# driver_32bit_v1_1.net
KiCad netlist of a schematic drawn in EAGLE
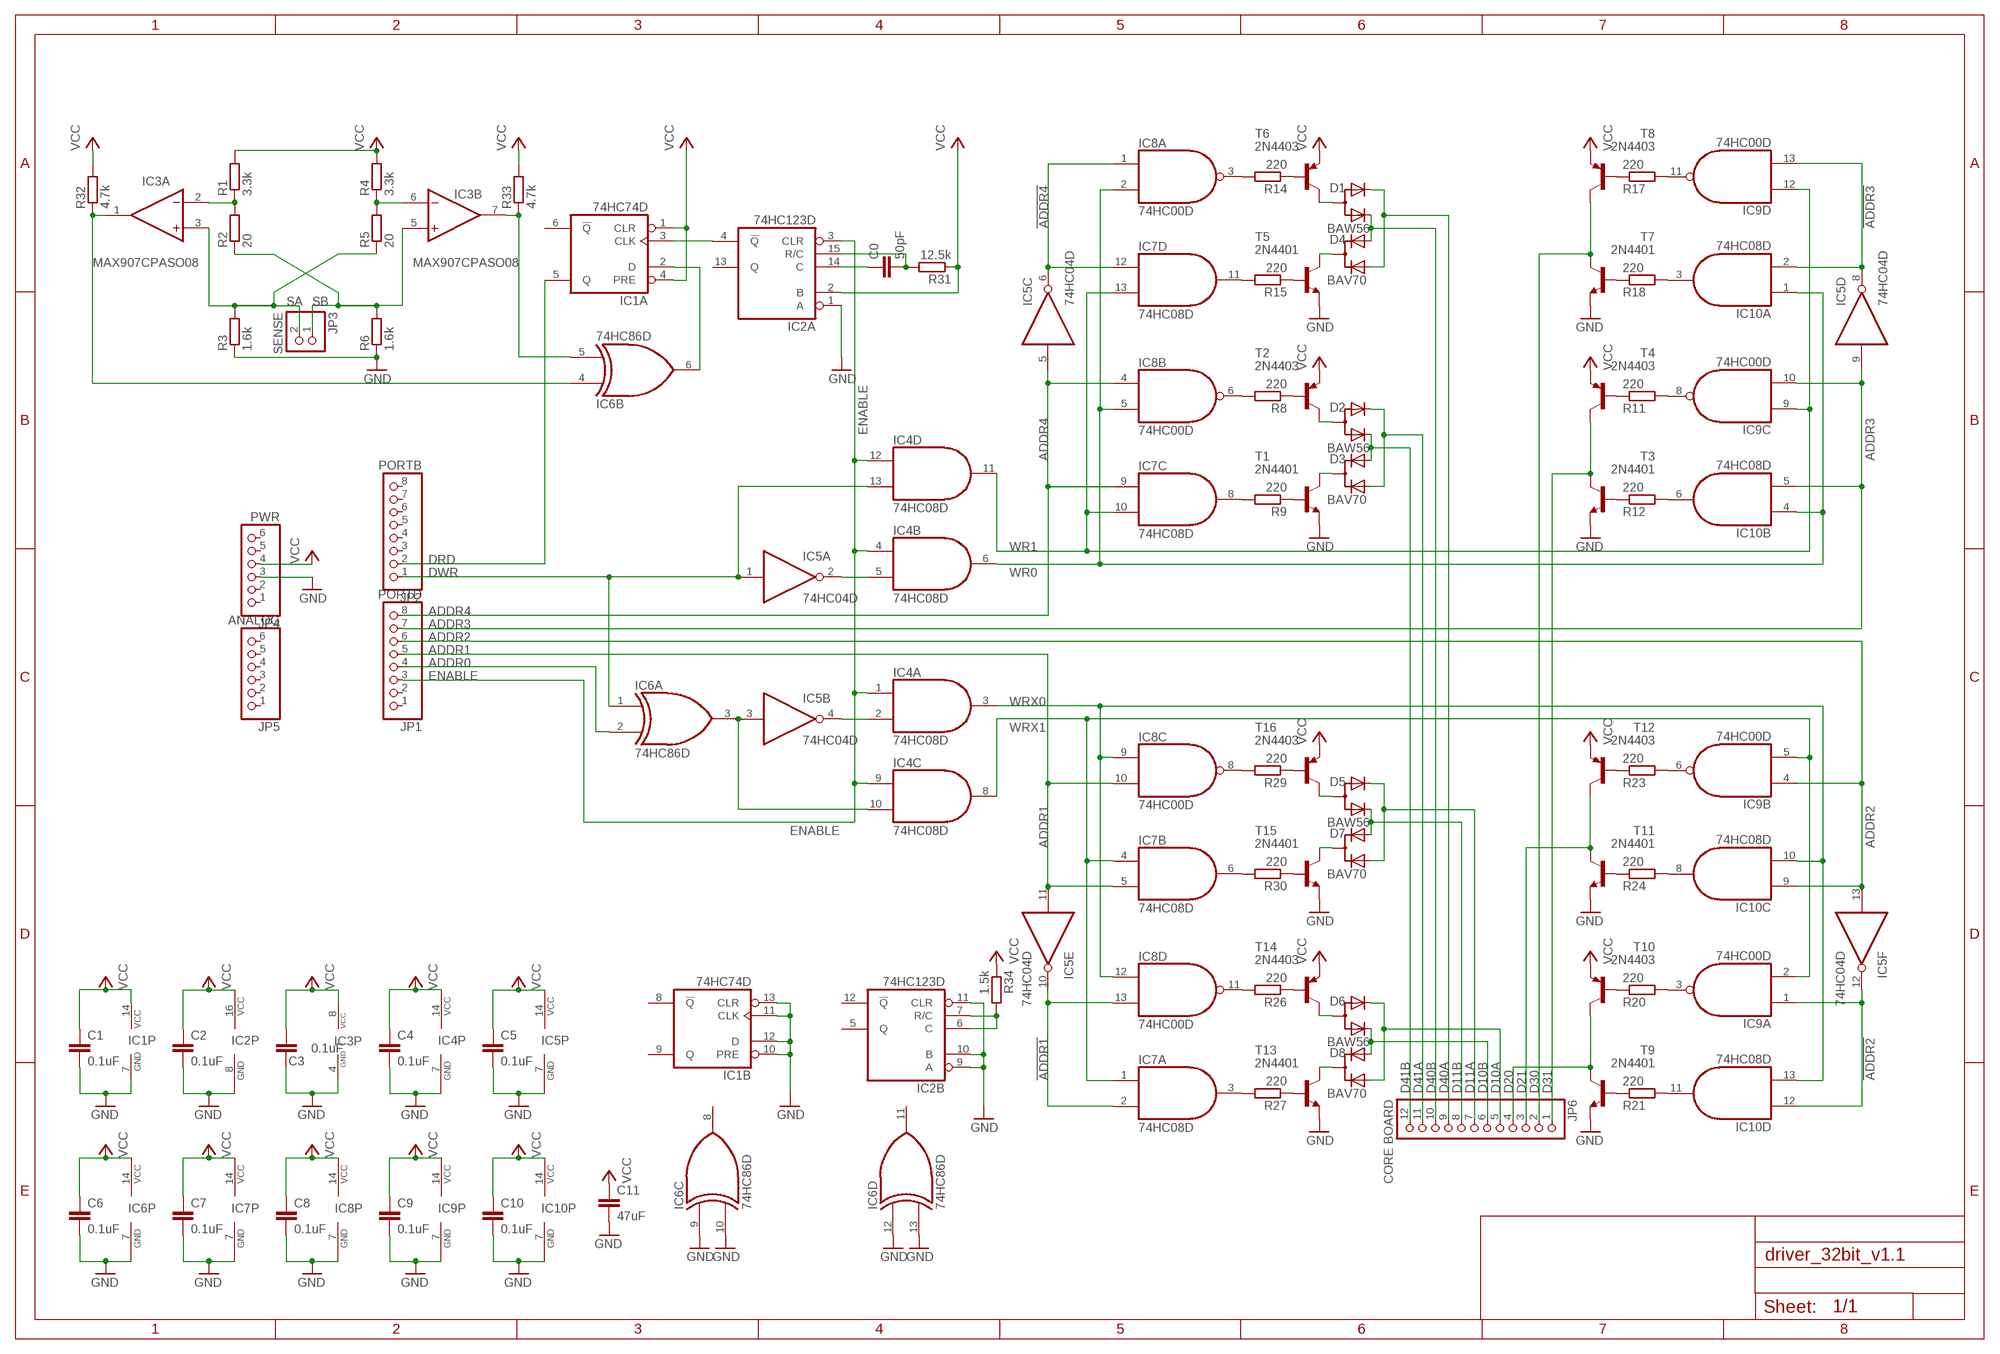
[diagram p0: schematic, sheet 1]

(export (version "E")
  (design (tool "Eeschema 10.0.6"))
  (components
    (comp (ref "C0")
      (value "50pF")
      (footprint "eagle-import:C1206")
      (libsource (lib "eagle-import") (part "C-EUC1206"))
    )
    (comp (ref "C1")
      (value "0.1uF")
      (footprint "eagle-import:C1206")
      (libsource (lib "eagle-import") (part "C-EUC1206"))
    )
    (comp (ref "C2")
      (value "0.1uF")
      (footprint "eagle-import:C1206")
      (libsource (lib "eagle-import") (part "C-EUC1206"))
    )
    (comp (ref "C3")
      (value "0.1uF")
      (footprint "eagle-import:C1206")
      (libsource (lib "eagle-import") (part "C-EUC1206"))
    )
    (comp (ref "C4")
      (value "0.1uF")
      (footprint "eagle-import:C1206")
      (libsource (lib "eagle-import") (part "C-EUC1206"))
    )
    (comp (ref "C5")
      (value "0.1uF")
      (footprint "eagle-import:C1206")
      (libsource (lib "eagle-import") (part "C-EUC1206"))
    )
    (comp (ref "C6")
      (value "0.1uF")
      (footprint "eagle-import:C1206")
      (libsource (lib "eagle-import") (part "C-EUC1206"))
    )
    (comp (ref "C7")
      (value "0.1uF")
      (footprint "eagle-import:C1206")
      (libsource (lib "eagle-import") (part "C-EUC1206"))
    )
    (comp (ref "C8")
      (value "0.1uF")
      (footprint "eagle-import:C1206")
      (libsource (lib "eagle-import") (part "C-EUC1206"))
    )
    (comp (ref "C9")
      (value "0.1uF")
      (footprint "eagle-import:C1206")
      (libsource (lib "eagle-import") (part "C-EUC1206"))
    )
    (comp (ref "C10")
      (value "0.1uF")
      (footprint "eagle-import:C1206")
      (libsource (lib "eagle-import") (part "C-EUC1206"))
    )
    (comp (ref "C11")
      (value "47uF")
      (footprint "eagle-import:C1206")
      (libsource (lib "eagle-import") (part "C-EUC1206"))
    )
    (comp (ref "D1")
      (value "BAW56")
      (footprint "eagle-import:SOT23")
      (libsource (lib "eagle-import") (part "DIODE-2CA|ACSOT23"))
    )
    (comp (ref "D2")
      (value "BAW56")
      (footprint "eagle-import:SOT23")
      (libsource (lib "eagle-import") (part "DIODE-2CA|ACSOT23"))
    )
    (comp (ref "D3")
      (value "BAV70")
      (footprint "eagle-import:SOT23")
      (libsource (lib "eagle-import") (part "DIODE-2AC|CASOT23"))
    )
    (comp (ref "D4")
      (value "BAV70")
      (footprint "eagle-import:SOT23")
      (libsource (lib "eagle-import") (part "DIODE-2AC|CASOT23"))
    )
    (comp (ref "D5")
      (value "BAW56")
      (footprint "eagle-import:SOT23")
      (libsource (lib "eagle-import") (part "DIODE-2CA|ACSOT23"))
    )
    (comp (ref "D6")
      (value "BAW56")
      (footprint "eagle-import:SOT23")
      (libsource (lib "eagle-import") (part "DIODE-2CA|ACSOT23"))
    )
    (comp (ref "D7")
      (value "BAV70")
      (footprint "eagle-import:SOT23")
      (libsource (lib "eagle-import") (part "DIODE-2AC|CASOT23"))
    )
    (comp (ref "D8")
      (value "BAV70")
      (footprint "eagle-import:SOT23")
      (libsource (lib "eagle-import") (part "DIODE-2AC|CASOT23"))
    )
    (comp (ref "IC1")
      (value "74HC74D")
      (footprint "eagle-import:SO14")
      (fields
        (field (name "MF") "TEXAS INSTRUMENTS")
        (field (name "MPN") "SN74HC74D")
        (field (name "OC_NEWARK") "08F6568")
      )
      (libsource (lib "eagle-import") (part "7474DHC"))
    )
    (comp (ref "IC2")
      (value "74HC123D")
      (footprint "eagle-import:SO16")
      (fields (field (name "MPN") "74HC123D") (field (name "OC_NEWARK") "99K0580"))
      (libsource (lib "eagle-import") (part "74123D"))
    )
    (comp (ref "IC3")
      (value "MAX907CPASO08")
      (footprint "eagle-import:SO08")
      (fields (field (name "OC_NEWARK") "unknown"))
      (libsource (lib "eagle-import") (part "MAX907CPASO08"))
    )
    (comp (ref "IC4")
      (value "74HC08D")
      (footprint "eagle-import:SO14")
      (fields
        (field (name "MF") "TEXAS INSTRUMENTS")
        (field (name "MPN") "SN74HC08D")
        (field (name "OC_NEWARK") "36K3552")
      )
      (libsource (lib "eagle-import") (part "7408DALS"))
    )
    (comp (ref "IC5")
      (value "74HC04D")
      (footprint "eagle-import:SO14")
      (fields
        (field (name "MF") "TEXAS INSTRUMENTS")
        (field (name "MPN") "SN74HC04D")
        (field (name "OC_NEWARK") "72K9430")
      )
      (libsource (lib "eagle-import") (part "7404DALS"))
    )
    (comp (ref "IC6")
      (value "74HC86D")
      (footprint "eagle-import:SO14")
      (fields (field (name "MPN") "74HC86D") (field (name "OC_NEWARK") "99K0602"))
      (libsource (lib "eagle-import") (part "7486DLS"))
    )
    (comp (ref "IC7")
      (value "74HC08D")
      (footprint "eagle-import:SO14")
      (fields
        (field (name "MF") "TEXAS INSTRUMENTS")
        (field (name "MPN") "SN74HC08D")
        (field (name "OC_NEWARK") "36K3552")
      )
      (libsource (lib "eagle-import") (part "7408DALS"))
    )
    (comp (ref "IC8")
      (value "74HC00D")
      (footprint "eagle-import:SO14")
      (fields (field (name "MPN") "74HC00D-Q100,118") (field (name "OC_NEWARK") "85X2859"))
      (libsource (lib "eagle-import") (part "7400DALS"))
    )
    (comp (ref "IC9")
      (value "74HC00D")
      (footprint "eagle-import:SO14")
      (fields (field (name "MPN") "74HC00D-Q100,118") (field (name "OC_NEWARK") "85X2859"))
      (libsource (lib "eagle-import") (part "7400DALS"))
    )
    (comp (ref "IC10")
      (value "74HC08D")
      (footprint "eagle-import:SO14")
      (fields
        (field (name "MF") "TEXAS INSTRUMENTS")
        (field (name "MPN") "SN74HC08D")
        (field (name "OC_NEWARK") "36K3552")
      )
      (libsource (lib "eagle-import") (part "7408DALS"))
    )
    (comp (ref "JP1")
      (value "PORTD")
      (footprint "eagle-import:1X08")
      (libsource (lib "eagle-import") (part "PINHD-1X8"))
    )
    (comp (ref "JP2")
      (value "PORTB")
      (footprint "eagle-import:1X08")
      (libsource (lib "eagle-import") (part "PINHD-1X8"))
    )
    (comp (ref "JP3")
      (value "SENSE")
      (footprint "eagle-import:1X02")
      (libsource (lib "eagle-import") (part "PINHD-1X2"))
    )
    (comp (ref "JP4")
      (value "PWR")
      (footprint "eagle-import:1X06")
      (libsource (lib "eagle-import") (part "PINHD-1X6"))
    )
    (comp (ref "JP5")
      (value "ANALOG")
      (footprint "eagle-import:1X06")
      (libsource (lib "eagle-import") (part "PINHD-1X6"))
    )
    (comp (ref "JP6")
      (value "CORE BOARD")
      (footprint "eagle-import:1X12")
      (libsource (lib "eagle-import") (part "PINHD-1X12"))
    )
    (comp (ref "R1")
      (value "3.3k")
      (footprint "eagle-import:R1206")
      (libsource (lib "eagle-import") (part "R-EU_R1206"))
    )
    (comp (ref "R2")
      (value "20")
      (footprint "eagle-import:R1206")
      (libsource (lib "eagle-import") (part "R-EU_R1206"))
    )
    (comp (ref "R3")
      (value "1.6k")
      (footprint "eagle-import:R1206")
      (libsource (lib "eagle-import") (part "R-EU_R1206"))
    )
    (comp (ref "R4")
      (value "3.3k")
      (footprint "eagle-import:R1206")
      (libsource (lib "eagle-import") (part "R-EU_R1206"))
    )
    (comp (ref "R5")
      (value "20")
      (footprint "eagle-import:R1206")
      (libsource (lib "eagle-import") (part "R-EU_R1206"))
    )
    (comp (ref "R6")
      (value "1.6k")
      (footprint "eagle-import:R1206")
      (libsource (lib "eagle-import") (part "R-EU_R1206"))
    )
    (comp (ref "R8")
      (value "220")
      (footprint "eagle-import:R1206")
      (libsource (lib "eagle-import") (part "R-EU_R1206"))
    )
    (comp (ref "R9")
      (value "220")
      (footprint "eagle-import:R1206")
      (libsource (lib "eagle-import") (part "R-EU_R1206"))
    )
    (comp (ref "R11")
      (value "220")
      (footprint "eagle-import:R1206")
      (libsource (lib "eagle-import") (part "R-EU_R1206"))
    )
    (comp (ref "R12")
      (value "220")
      (footprint "eagle-import:R1206")
      (libsource (lib "eagle-import") (part "R-EU_R1206"))
    )
    (comp (ref "R14")
      (value "220")
      (footprint "eagle-import:R1206")
      (libsource (lib "eagle-import") (part "R-EU_R1206"))
    )
    (comp (ref "R15")
      (value "220")
      (footprint "eagle-import:R1206")
      (libsource (lib "eagle-import") (part "R-EU_R1206"))
    )
    (comp (ref "R17")
      (value "220")
      (footprint "eagle-import:R1206")
      (libsource (lib "eagle-import") (part "R-EU_R1206"))
    )
    (comp (ref "R18")
      (value "220")
      (footprint "eagle-import:R1206")
      (libsource (lib "eagle-import") (part "R-EU_R1206"))
    )
    (comp (ref "R20")
      (value "220")
      (footprint "eagle-import:R1206")
      (libsource (lib "eagle-import") (part "R-EU_R1206"))
    )
    (comp (ref "R21")
      (value "220")
      (footprint "eagle-import:R1206")
      (libsource (lib "eagle-import") (part "R-EU_R1206"))
    )
    (comp (ref "R23")
      (value "220")
      (footprint "eagle-import:R1206")
      (libsource (lib "eagle-import") (part "R-EU_R1206"))
    )
    (comp (ref "R24")
      (value "220")
      (footprint "eagle-import:R1206")
      (libsource (lib "eagle-import") (part "R-EU_R1206"))
    )
    (comp (ref "R26")
      (value "220")
      (footprint "eagle-import:R1206")
      (libsource (lib "eagle-import") (part "R-EU_R1206"))
    )
    (comp (ref "R27")
      (value "220")
      (footprint "eagle-import:R1206")
      (libsource (lib "eagle-import") (part "R-EU_R1206"))
    )
    (comp (ref "R29")
      (value "220")
      (footprint "eagle-import:R1206")
      (libsource (lib "eagle-import") (part "R-EU_R1206"))
    )
    (comp (ref "R30")
      (value "220")
      (footprint "eagle-import:R1206")
      (libsource (lib "eagle-import") (part "R-EU_R1206"))
    )
    (comp (ref "R31")
      (value "12.5k")
      (footprint "eagle-import:R1206")
      (libsource (lib "eagle-import") (part "R-EU_R1206"))
    )
    (comp (ref "R32")
      (value "4.7k")
      (footprint "eagle-import:R1206")
      (libsource (lib "eagle-import") (part "R-EU_R1206"))
    )
    (comp (ref "R33")
      (value "4.7k")
      (footprint "eagle-import:R1206")
      (libsource (lib "eagle-import") (part "R-EU_R1206"))
    )
    (comp (ref "R34")
      (value "1.5k")
      (footprint "eagle-import:R1206")
      (libsource (lib "eagle-import") (part "R-EU_R1206"))
    )
    (comp (ref "T1")
      (value "2N4401")
      (footprint "eagle-import:SOT23-BEC")
      (fields (field (name "MF") "ON SEMICONDUCTOR") (field (name "MPN") "2N4401RLRPG"))
      (libsource (lib "eagle-import") (part "-NPN-SOT23-BECMMBT4401LT1"))
    )
    (comp (ref "T2")
      (value "2N4403")
      (footprint "eagle-import:SOT23-BEC")
      (libsource (lib "eagle-import") (part "-PNP-SOT23-BECMMBT4403LT1"))
    )
    (comp (ref "T3")
      (value "2N4401")
      (footprint "eagle-import:SOT23-BEC")
      (fields (field (name "MF") "ON SEMICONDUCTOR") (field (name "MPN") "2N4401RLRPG"))
      (libsource (lib "eagle-import") (part "-NPN-SOT23-BECMMBT4401LT1"))
    )
    (comp (ref "T4")
      (value "2N4403")
      (footprint "eagle-import:SOT23-BEC")
      (libsource (lib "eagle-import") (part "-PNP-SOT23-BECMMBT4403LT1"))
    )
    (comp (ref "T5")
      (value "2N4401")
      (footprint "eagle-import:SOT23-BEC")
      (fields (field (name "MF") "ON SEMICONDUCTOR") (field (name "MPN") "2N4401RLRPG"))
      (libsource (lib "eagle-import") (part "-NPN-SOT23-BECMMBT4401LT1"))
    )
    (comp (ref "T6")
      (value "2N4403")
      (footprint "eagle-import:SOT23-BEC")
      (libsource (lib "eagle-import") (part "-PNP-SOT23-BECMMBT4403LT1"))
    )
    (comp (ref "T7")
      (value "2N4401")
      (footprint "eagle-import:SOT23-BEC")
      (fields (field (name "MF") "ON SEMICONDUCTOR") (field (name "MPN") "2N4401RLRPG"))
      (libsource (lib "eagle-import") (part "-NPN-SOT23-BECMMBT4401LT1"))
    )
    (comp (ref "T8")
      (value "2N4403")
      (footprint "eagle-import:SOT23-BEC")
      (libsource (lib "eagle-import") (part "-PNP-SOT23-BECMMBT4403LT1"))
    )
    (comp (ref "T9")
      (value "2N4401")
      (footprint "eagle-import:SOT23-BEC")
      (fields (field (name "MF") "ON SEMICONDUCTOR") (field (name "MPN") "2N4401RLRPG"))
      (libsource (lib "eagle-import") (part "-NPN-SOT23-BECMMBT4401LT1"))
    )
    (comp (ref "T10")
      (value "2N4403")
      (footprint "eagle-import:SOT23-BEC")
      (libsource (lib "eagle-import") (part "-PNP-SOT23-BECMMBT4403LT1"))
    )
    (comp (ref "T11")
      (value "2N4401")
      (footprint "eagle-import:SOT23-BEC")
      (fields (field (name "MF") "ON SEMICONDUCTOR") (field (name "MPN") "2N4401RLRPG"))
      (libsource (lib "eagle-import") (part "-NPN-SOT23-BECMMBT4401LT1"))
    )
    (comp (ref "T12")
      (value "2N4403")
      (footprint "eagle-import:SOT23-BEC")
      (libsource (lib "eagle-import") (part "-PNP-SOT23-BECMMBT4403LT1"))
    )
    (comp (ref "T13")
      (value "2N4401")
      (footprint "eagle-import:SOT23-BEC")
      (fields (field (name "MF") "ON SEMICONDUCTOR") (field (name "MPN") "2N4401RLRPG"))
      (libsource (lib "eagle-import") (part "-NPN-SOT23-BECMMBT4401LT1"))
    )
    (comp (ref "T14")
      (value "2N4403")
      (footprint "eagle-import:SOT23-BEC")
      (libsource (lib "eagle-import") (part "-PNP-SOT23-BECMMBT4403LT1"))
    )
    (comp (ref "T15")
      (value "2N4401")
      (footprint "eagle-import:SOT23-BEC")
      (fields (field (name "MF") "ON SEMICONDUCTOR") (field (name "MPN") "2N4401RLRPG"))
      (libsource (lib "eagle-import") (part "-NPN-SOT23-BECMMBT4401LT1"))
    )
    (comp (ref "T16")
      (value "2N4403")
      (footprint "eagle-import:SOT23-BEC")
      (libsource (lib "eagle-import") (part "-PNP-SOT23-BECMMBT4403LT1"))
    )
  )
  (nets
    (net (code "1") (name "/ADDR0") (class "Default")
      (node (ref "IC6") (pin "2") (pinfunction "I1_2") (pintype "input"))
      (node (ref "JP1") (pin "4") (pinfunction "4_4") (pintype "passive"))
    )
    (net (code "2") (name "/ADDR1") (class "Default")
      (node (ref "IC5") (pin "11") (pinfunction "I_11") (pintype "input"))
      (node (ref "IC7") (pin "5") (pinfunction "I1_5") (pintype "input"))
      (node (ref "IC8") (pin "10") (pinfunction "I1_10") (pintype "input"))
      (node (ref "JP1") (pin "5") (pinfunction "5_5") (pintype "passive"))
    )
    (net (code "3") (name "/ADDR2") (class "Default")
      (node (ref "IC10") (pin "9") (pinfunction "I0_9") (pintype "input"))
      (node (ref "IC5") (pin "13") (pinfunction "I_13") (pintype "input"))
      (node (ref "IC9") (pin "4") (pinfunction "I0_4") (pintype "input"))
      (node (ref "JP1") (pin "6") (pinfunction "6_6") (pintype "passive"))
    )
    (net (code "4") (name "/ADDR3") (class "Default")
      (node (ref "IC10") (pin "5") (pinfunction "I1_5") (pintype "input"))
      (node (ref "IC5") (pin "9") (pinfunction "I_9") (pintype "input"))
      (node (ref "IC9") (pin "10") (pinfunction "I1_10") (pintype "input"))
      (node (ref "JP1") (pin "7") (pinfunction "7_7") (pintype "passive"))
    )
    (net (code "5") (name "/ADDR4") (class "Default")
      (node (ref "IC5") (pin "5") (pinfunction "I_5") (pintype "input"))
      (node (ref "IC7") (pin "9") (pinfunction "I0_9") (pintype "input"))
      (node (ref "IC8") (pin "4") (pinfunction "I0_4") (pintype "input"))
      (node (ref "JP1") (pin "8") (pinfunction "8_8") (pintype "passive"))
    )
    (net (code "6") (name "/D10A") (class "Default")
      (node (ref "D6") (pin "1") (pinfunction "K2_1") (pintype "passive"))
      (node (ref "D8") (pin "2") (pinfunction "A2_2") (pintype "passive"))
      (node (ref "JP6") (pin "5") (pinfunction "5_5") (pintype "passive"))
    )
    (net (code "7") (name "/D10B") (class "Default")
      (node (ref "D6") (pin "2") (pinfunction "K1_2") (pintype "passive"))
      (node (ref "D8") (pin "1") (pinfunction "A1_1") (pintype "passive"))
      (node (ref "JP6") (pin "6") (pinfunction "6_6") (pintype "passive"))
    )
    (net (code "8") (name "/D11A") (class "Default")
      (node (ref "D5") (pin "1") (pinfunction "K2_1") (pintype "passive"))
      (node (ref "D7") (pin "2") (pinfunction "A2_2") (pintype "passive"))
      (node (ref "JP6") (pin "7") (pinfunction "7_7") (pintype "passive"))
    )
    (net (code "9") (name "/D11B") (class "Default")
      (node (ref "D5") (pin "2") (pinfunction "K1_2") (pintype "passive"))
      (node (ref "D7") (pin "1") (pinfunction "A1_1") (pintype "passive"))
      (node (ref "JP6") (pin "8") (pinfunction "8_8") (pintype "passive"))
    )
    (net (code "10") (name "/D20") (class "Default")
      (node (ref "JP6") (pin "4") (pinfunction "4_4") (pintype "passive"))
      (node (ref "T10") (pin "C") (pinfunction "C_C") (pintype "passive"))
      (node (ref "T9") (pin "C") (pinfunction "C_C") (pintype "passive"))
    )
    (net (code "11") (name "/D21") (class "Default")
      (node (ref "JP6") (pin "3") (pinfunction "3_3") (pintype "passive"))
      (node (ref "T11") (pin "C") (pinfunction "C_C") (pintype "passive"))
      (node (ref "T12") (pin "C") (pinfunction "C_C") (pintype "passive"))
    )
    (net (code "12") (name "/D30") (class "Default")
      (node (ref "JP6") (pin "2") (pinfunction "2_2") (pintype "passive"))
      (node (ref "T7") (pin "C") (pinfunction "C_C") (pintype "passive"))
      (node (ref "T8") (pin "C") (pinfunction "C_C") (pintype "passive"))
    )
    (net (code "13") (name "/D31") (class "Default")
      (node (ref "JP6") (pin "1") (pinfunction "1_1") (pintype "passive"))
      (node (ref "T3") (pin "C") (pinfunction "C_C") (pintype "passive"))
      (node (ref "T4") (pin "C") (pinfunction "C_C") (pintype "passive"))
    )
    (net (code "14") (name "/D40A") (class "Default")
      (node (ref "D1") (pin "1") (pinfunction "K2_1") (pintype "passive"))
      (node (ref "D4") (pin "2") (pinfunction "A2_2") (pintype "passive"))
      (node (ref "JP6") (pin "9") (pinfunction "9_9") (pintype "passive"))
    )
    (net (code "15") (name "/D40B") (class "Default")
      (node (ref "D1") (pin "2") (pinfunction "K1_2") (pintype "passive"))
      (node (ref "D4") (pin "1") (pinfunction "A1_1") (pintype "passive"))
      (node (ref "JP6") (pin "10") (pinfunction "10_10") (pintype "passive"))
    )
    (net (code "16") (name "/D41A") (class "Default")
      (node (ref "D2") (pin "1") (pinfunction "K2_1") (pintype "passive"))
      (node (ref "D3") (pin "2") (pinfunction "A2_2") (pintype "passive"))
      (node (ref "JP6") (pin "11") (pinfunction "11_11") (pintype "passive"))
    )
    (net (code "17") (name "/D41B") (class "Default")
      (node (ref "D2") (pin "2") (pinfunction "K1_2") (pintype "passive"))
      (node (ref "D3") (pin "1") (pinfunction "A1_1") (pintype "passive"))
      (node (ref "JP6") (pin "12") (pinfunction "12_12") (pintype "passive"))
    )
    (net (code "18") (name "/DRD") (class "Default")
      (node (ref "IC1") (pin "5") (pinfunction "Q_5") (pintype "output"))
      (node (ref "JP2") (pin "2") (pinfunction "2_2") (pintype "passive"))
    )
    (net (code "19") (name "/DWR") (class "Default")
      (node (ref "IC4") (pin "13") (pinfunction "I1_13") (pintype "input"))
      (node (ref "IC5") (pin "1") (pinfunction "I_1") (pintype "input"))
      (node (ref "IC6") (pin "1") (pinfunction "I0_1") (pintype "input"))
      (node (ref "JP2") (pin "1") (pinfunction "1_1") (pintype "passive"))
    )
    (net (code "20") (name "/ENABLE") (class "Default")
      (node (ref "IC2") (pin "3") (pinfunction "CLR_3") (pintype "input"))
      (node (ref "IC4") (pin "1") (pinfunction "I0_1") (pintype "input"))
      (node (ref "IC4") (pin "12") (pinfunction "I0_12") (pintype "input"))
      (node (ref "IC4") (pin "4") (pinfunction "I0_4") (pintype "input"))
      (node (ref "IC4") (pin "9") (pinfunction "I0_9") (pintype "input"))
      (node (ref "JP1") (pin "3") (pinfunction "3_3") (pintype "passive"))
    )
    (net (code "21") (name "/SA") (class "Default")
      (node (ref "IC3") (pin "3") (pinfunction "+IN_3") (pintype "input"))
      (node (ref "JP3") (pin "2") (pinfunction "2_2") (pintype "passive"))
      (node (ref "R3") (pin "2") (pinfunction "2_2") (pintype "passive"))
      (node (ref "R5") (pin "1") (pinfunction "1_1") (pintype "passive"))
    )
    (net (code "22") (name "/SB") (class "Default")
      (node (ref "IC3") (pin "5") (pinfunction "+IN_5") (pintype "input"))
      (node (ref "JP3") (pin "1") (pinfunction "1_1") (pintype "passive"))
      (node (ref "R2") (pin "1") (pinfunction "1_1") (pintype "passive"))
      (node (ref "R6") (pin "2") (pinfunction "2_2") (pintype "passive"))
    )
    (net (code "23") (name "/WR0") (class "Default")
      (node (ref "IC10") (pin "1") (pinfunction "I0_1") (pintype "input"))
      (node (ref "IC10") (pin "4") (pinfunction "I0_4") (pintype "input"))
      (node (ref "IC4") (pin "6") (pinfunction "O_6") (pintype "output"))
      (node (ref "IC8") (pin "2") (pinfunction "I1_2") (pintype "input"))
      (node (ref "IC8") (pin "5") (pinfunction "I1_5") (pintype "input"))
    )
    (net (code "24") (name "/WR1") (class "Default")
      (node (ref "IC4") (pin "11") (pinfunction "O_11") (pintype "output"))
      (node (ref "IC7") (pin "10") (pinfunction "I1_10") (pintype "input"))
      (node (ref "IC7") (pin "13") (pinfunction "I1_13") (pintype "input"))
      (node (ref "IC9") (pin "12") (pinfunction "I0_12") (pintype "input"))
      (node (ref "IC9") (pin "9") (pinfunction "I0_9") (pintype "input"))
    )
    (net (code "25") (name "/WRX0") (class "Default")
      (node (ref "IC10") (pin "10") (pinfunction "I1_10") (pintype "input"))
      (node (ref "IC10") (pin "13") (pinfunction "I1_13") (pintype "input"))
      (node (ref "IC4") (pin "3") (pinfunction "O_3") (pintype "output"))
      (node (ref "IC8") (pin "12") (pinfunction "I0_12") (pintype "input"))
      (node (ref "IC8") (pin "9") (pinfunction "I0_9") (pintype "input"))
    )
    (net (code "26") (name "/WRX1") (class "Default")
      (node (ref "IC4") (pin "8") (pinfunction "O_8") (pintype "output"))
      (node (ref "IC7") (pin "1") (pinfunction "I0_1") (pintype "input"))
      (node (ref "IC7") (pin "4") (pinfunction "I0_4") (pintype "input"))
      (node (ref "IC9") (pin "2") (pinfunction "I1_2") (pintype "input"))
      (node (ref "IC9") (pin "5") (pinfunction "I1_5") (pintype "input"))
    )
    (net (code "27") (name "/~{ADDR1}") (class "Default")
      (node (ref "IC5") (pin "10") (pinfunction "O_10") (pintype "output"))
      (node (ref "IC7") (pin "2") (pinfunction "I1_2") (pintype "input"))
      (node (ref "IC8") (pin "13") (pinfunction "I1_13") (pintype "input"))
    )
    (net (code "28") (name "/~{ADDR2}") (class "Default")
      (node (ref "IC10") (pin "12") (pinfunction "I0_12") (pintype "input"))
      (node (ref "IC5") (pin "12") (pinfunction "O_12") (pintype "output"))
      (node (ref "IC9") (pin "1") (pinfunction "I0_1") (pintype "input"))
    )
    (net (code "29") (name "/~{ADDR3}") (class "Default")
      (node (ref "IC10") (pin "2") (pinfunction "I1_2") (pintype "input"))
      (node (ref "IC5") (pin "8") (pinfunction "O_8") (pintype "output"))
      (node (ref "IC9") (pin "13") (pinfunction "I1_13") (pintype "input"))
    )
    (net (code "30") (name "/~{ADDR4}") (class "Default")
      (node (ref "IC5") (pin "6") (pinfunction "O_6") (pintype "output"))
      (node (ref "IC7") (pin "12") (pinfunction "I0_12") (pintype "input"))
      (node (ref "IC8") (pin "1") (pinfunction "I0_1") (pintype "input"))
    )
    (net (code "31") (name "GND") (class "Default")
      (node (ref "C1") (pin "2") (pinfunction "2_2") (pintype "passive"))
      (node (ref "C10") (pin "2") (pinfunction "2_2") (pintype "passive"))
      (node (ref "C11") (pin "2") (pinfunction "2_2") (pintype "passive"))
      (node (ref "C2") (pin "2") (pinfunction "2_2") (pintype "passive"))
      (node (ref "C3") (pin "1") (pinfunction "1_1") (pintype "passive"))
      (node (ref "C4") (pin "2") (pinfunction "2_2") (pintype "passive"))
      (node (ref "C5") (pin "2") (pinfunction "2_2") (pintype "passive"))
      (node (ref "C6") (pin "2") (pinfunction "2_2") (pintype "passive"))
      (node (ref "C7") (pin "2") (pinfunction "2_2") (pintype "passive"))
      (node (ref "C8") (pin "2") (pinfunction "2_2") (pintype "passive"))
      (node (ref "C9") (pin "2") (pinfunction "2_2") (pintype "passive"))
      (node (ref "IC1") (pin "10") (pinfunction "PRE_10") (pintype "input"))
      (node (ref "IC1") (pin "11") (pinfunction "CLK_11") (pintype "input"))
      (node (ref "IC1") (pin "12") (pinfunction "D_12") (pintype "input"))
      (node (ref "IC1") (pin "13") (pinfunction "CLR_13") (pintype "input"))
      (node (ref "IC1") (pin "7") (pinfunction "GND_7") (pintype "power_in"))
      (node (ref "IC10") (pin "7") (pinfunction "GND_7") (pintype "power_in"))
      (node (ref "IC2") (pin "1") (pinfunction "A_1") (pintype "input"))
      (node (ref "IC2") (pin "10") (pinfunction "B_10") (pintype "input"))
      (node (ref "IC2") (pin "11") (pinfunction "CLR_11") (pintype "input"))
      (node (ref "IC2") (pin "8") (pinfunction "GND_8") (pintype "power_in"))
      (node (ref "IC2") (pin "9") (pinfunction "A_9") (pintype "input"))
      (node (ref "IC3") (pin "4") (pinfunction "GND_4") (pintype "power_in"))
      (node (ref "IC4") (pin "7") (pinfunction "GND_7") (pintype "power_in"))
      (node (ref "IC5") (pin "7") (pinfunction "GND_7") (pintype "power_in"))
      (node (ref "IC6") (pin "10") (pinfunction "I1_10") (pintype "input"))
      (node (ref "IC6") (pin "12") (pinfunction "I0_12") (pintype "input"))
      (node (ref "IC6") (pin "13") (pinfunction "I1_13") (pintype "input"))
      (node (ref "IC6") (pin "7") (pinfunction "GND_7") (pintype "power_in"))
      (node (ref "IC6") (pin "9") (pinfunction "I0_9") (pintype "input"))
      (node (ref "IC7") (pin "7") (pinfunction "GND_7") (pintype "power_in"))
      (node (ref "IC8") (pin "7") (pinfunction "GND_7") (pintype "power_in"))
      (node (ref "IC9") (pin "7") (pinfunction "GND_7") (pintype "power_in"))
      (node (ref "JP4") (pin "3") (pinfunction "3_3") (pintype "passive"))
      (node (ref "R3") (pin "1") (pinfunction "1_1") (pintype "passive"))
      (node (ref "R6") (pin "1") (pinfunction "1_1") (pintype "passive"))
      (node (ref "T1") (pin "E") (pinfunction "E_E") (pintype "passive"))
      (node (ref "T11") (pin "E") (pinfunction "E_E") (pintype "passive"))
      (node (ref "T13") (pin "E") (pinfunction "E_E") (pintype "passive"))
      (node (ref "T15") (pin "E") (pinfunction "E_E") (pintype "passive"))
      (node (ref "T3") (pin "E") (pinfunction "E_E") (pintype "passive"))
      (node (ref "T5") (pin "E") (pinfunction "E_E") (pintype "passive"))
      (node (ref "T7") (pin "E") (pinfunction "E_E") (pintype "passive"))
      (node (ref "T9") (pin "E") (pinfunction "E_E") (pintype "passive"))
    )
    (net (code "32") (name "Net-(D1-A)") (class "Default")
      (node (ref "D1") (pin "3") (pinfunction "A_3") (pintype "passive"))
      (node (ref "T6") (pin "C") (pinfunction "C_C") (pintype "passive"))
    )
    (net (code "33") (name "Net-(D2-A)") (class "Default")
      (node (ref "D2") (pin "3") (pinfunction "A_3") (pintype "passive"))
      (node (ref "T2") (pin "C") (pinfunction "C_C") (pintype "passive"))
    )
    (net (code "34") (name "Net-(D3-C)") (class "Default")
      (node (ref "D3") (pin "3") (pinfunction "C_3") (pintype "passive"))
      (node (ref "T1") (pin "C") (pinfunction "C_C") (pintype "passive"))
    )
    (net (code "35") (name "Net-(D4-C)") (class "Default")
      (node (ref "D4") (pin "3") (pinfunction "C_3") (pintype "passive"))
      (node (ref "T5") (pin "C") (pinfunction "C_C") (pintype "passive"))
    )
    (net (code "36") (name "Net-(D5-A)") (class "Default")
      (node (ref "D5") (pin "3") (pinfunction "A_3") (pintype "passive"))
      (node (ref "T16") (pin "C") (pinfunction "C_C") (pintype "passive"))
    )
    (net (code "37") (name "Net-(D6-A)") (class "Default")
      (node (ref "D6") (pin "3") (pinfunction "A_3") (pintype "passive"))
      (node (ref "T14") (pin "C") (pinfunction "C_C") (pintype "passive"))
    )
    (net (code "38") (name "Net-(D7-C)") (class "Default")
      (node (ref "D7") (pin "3") (pinfunction "C_3") (pintype "passive"))
      (node (ref "T15") (pin "C") (pinfunction "C_C") (pintype "passive"))
    )
    (net (code "39") (name "Net-(D8-C)") (class "Default")
      (node (ref "D8") (pin "3") (pinfunction "C_3") (pintype "passive"))
      (node (ref "T13") (pin "C") (pinfunction "C_C") (pintype "passive"))
    )
    (net (code "40") (name "Net-(IC1A-CLK)") (class "Default")
      (node (ref "IC1") (pin "3") (pinfunction "CLK_3") (pintype "input"))
      (node (ref "IC2") (pin "4") (pinfunction "~{Q}_4") (pintype "output"))
    )
    (net (code "41") (name "Net-(IC1A-D)") (class "Default")
      (node (ref "IC1") (pin "2") (pinfunction "D_2") (pintype "input"))
      (node (ref "IC6") (pin "6") (pinfunction "O_6") (pintype "output"))
    )
    (net (code "42") (name "Net-(IC2A-C)") (class "Default")
      (node (ref "C0") (pin "1") (pinfunction "1_1") (pintype "passive"))
      (node (ref "IC2") (pin "14") (pinfunction "C_14") (pintype "input"))
    )
    (net (code "43") (name "Net-(IC2A-R{slash}C)") (class "Default")
      (node (ref "C0") (pin "2") (pinfunction "2_2") (pintype "passive"))
      (node (ref "IC2") (pin "15") (pinfunction "R/C_15") (pintype "input"))
      (node (ref "R31") (pin "2") (pinfunction "2_2") (pintype "passive"))
    )
    (net (code "44") (name "Net-(IC2B-C)") (class "Default")
      (node (ref "IC2") (pin "6") (pinfunction "C_6") (pintype "input"))
      (node (ref "IC2") (pin "7") (pinfunction "R/C_7") (pintype "input"))
      (node (ref "R34") (pin "2") (pinfunction "2_2") (pintype "passive"))
    )
    (net (code "45") (name "Net-(IC3A--IN)") (class "Default")
      (node (ref "IC3") (pin "2") (pinfunction "-IN_2") (pintype "input"))
      (node (ref "R1") (pin "1") (pinfunction "1_1") (pintype "passive"))
      (node (ref "R2") (pin "2") (pinfunction "2_2") (pintype "passive"))
    )
    (net (code "46") (name "Net-(IC3A-OUT)") (class "Default")
      (node (ref "IC3") (pin "1") (pinfunction "OUT_1") (pintype "output"))
      (node (ref "IC6") (pin "4") (pinfunction "I0_4") (pintype "input"))
      (node (ref "R32") (pin "1") (pinfunction "1_1") (pintype "passive"))
    )
    (net (code "47") (name "Net-(IC3B--IN)") (class "Default")
      (node (ref "IC3") (pin "6") (pinfunction "-IN_6") (pintype "input"))
      (node (ref "R4") (pin "1") (pinfunction "1_1") (pintype "passive"))
      (node (ref "R5") (pin "2") (pinfunction "2_2") (pintype "passive"))
    )
    (net (code "48") (name "Net-(IC3B-OUT)") (class "Default")
      (node (ref "IC3") (pin "7") (pinfunction "OUT_7") (pintype "output"))
      (node (ref "IC6") (pin "5") (pinfunction "I1_5") (pintype "input"))
      (node (ref "R33") (pin "1") (pinfunction "1_1") (pintype "passive"))
    )
    (net (code "49") (name "Net-(IC4A-I1)") (class "Default")
      (node (ref "IC4") (pin "2") (pinfunction "I1_2") (pintype "input"))
      (node (ref "IC5") (pin "4") (pinfunction "O_4") (pintype "output"))
    )
    (net (code "50") (name "Net-(IC4B-I1)") (class "Default")
      (node (ref "IC4") (pin "5") (pinfunction "I1_5") (pintype "input"))
      (node (ref "IC5") (pin "2") (pinfunction "O_2") (pintype "output"))
    )
    (net (code "51") (name "Net-(IC4C-I1)") (class "Default")
      (node (ref "IC4") (pin "10") (pinfunction "I1_10") (pintype "input"))
      (node (ref "IC5") (pin "3") (pinfunction "I_3") (pintype "input"))
      (node (ref "IC6") (pin "3") (pinfunction "O_3") (pintype "output"))
    )
    (net (code "52") (name "Net-(IC7A-O)") (class "Default")
      (node (ref "IC7") (pin "3") (pinfunction "O_3") (pintype "output"))
      (node (ref "R27") (pin "2") (pinfunction "2_2") (pintype "passive"))
    )
    (net (code "53") (name "Net-(IC7B-O)") (class "Default")
      (node (ref "IC7") (pin "6") (pinfunction "O_6") (pintype "output"))
      (node (ref "R30") (pin "2") (pinfunction "2_2") (pintype "passive"))
    )
    (net (code "54") (name "Net-(IC7C-O)") (class "Default")
      (node (ref "IC7") (pin "8") (pinfunction "O_8") (pintype "output"))
      (node (ref "R9") (pin "2") (pinfunction "2_2") (pintype "passive"))
    )
    (net (code "55") (name "Net-(IC7D-O)") (class "Default")
      (node (ref "IC7") (pin "11") (pinfunction "O_11") (pintype "output"))
      (node (ref "R15") (pin "2") (pinfunction "2_2") (pintype "passive"))
    )
    (net (code "56") (name "Net-(IC8A-O)") (class "Default")
      (node (ref "IC8") (pin "3") (pinfunction "O_3") (pintype "output"))
      (node (ref "R14") (pin "2") (pinfunction "2_2") (pintype "passive"))
    )
    (net (code "57") (name "Net-(IC8B-O)") (class "Default")
      (node (ref "IC8") (pin "6") (pinfunction "O_6") (pintype "output"))
      (node (ref "R8") (pin "2") (pinfunction "2_2") (pintype "passive"))
    )
    (net (code "58") (name "Net-(IC8C-O)") (class "Default")
      (node (ref "IC8") (pin "8") (pinfunction "O_8") (pintype "output"))
      (node (ref "R29") (pin "2") (pinfunction "2_2") (pintype "passive"))
    )
    (net (code "59") (name "Net-(IC8D-O)") (class "Default")
      (node (ref "IC8") (pin "11") (pinfunction "O_11") (pintype "output"))
      (node (ref "R26") (pin "2") (pinfunction "2_2") (pintype "passive"))
    )
    (net (code "60") (name "Net-(IC9A-O)") (class "Default")
      (node (ref "IC9") (pin "3") (pinfunction "O_3") (pintype "output"))
      (node (ref "R20") (pin "2") (pinfunction "2_2") (pintype "passive"))
    )
    (net (code "61") (name "Net-(IC9B-O)") (class "Default")
      (node (ref "IC9") (pin "6") (pinfunction "O_6") (pintype "output"))
      (node (ref "R23") (pin "2") (pinfunction "2_2") (pintype "passive"))
    )
    (net (code "62") (name "Net-(IC9C-O)") (class "Default")
      (node (ref "IC9") (pin "8") (pinfunction "O_8") (pintype "output"))
      (node (ref "R11") (pin "2") (pinfunction "2_2") (pintype "passive"))
    )
    (net (code "63") (name "Net-(IC9D-O)") (class "Default")
      (node (ref "IC9") (pin "11") (pinfunction "O_11") (pintype "output"))
      (node (ref "R17") (pin "2") (pinfunction "2_2") (pintype "passive"))
    )
    (net (code "64") (name "Net-(IC10A-O)") (class "Default")
      (node (ref "IC10") (pin "3") (pinfunction "O_3") (pintype "output"))
      (node (ref "R18") (pin "2") (pinfunction "2_2") (pintype "passive"))
    )
    (net (code "65") (name "Net-(IC10B-O)") (class "Default")
      (node (ref "IC10") (pin "6") (pinfunction "O_6") (pintype "output"))
      (node (ref "R12") (pin "2") (pinfunction "2_2") (pintype "passive"))
    )
    (net (code "66") (name "Net-(IC10C-O)") (class "Default")
      (node (ref "IC10") (pin "8") (pinfunction "O_8") (pintype "output"))
      (node (ref "R24") (pin "2") (pinfunction "2_2") (pintype "passive"))
    )
    (net (code "67") (name "Net-(IC10D-O)") (class "Default")
      (node (ref "IC10") (pin "11") (pinfunction "O_11") (pintype "output"))
      (node (ref "R21") (pin "2") (pinfunction "2_2") (pintype "passive"))
    )
    (net (code "68") (name "Net-(R8-Pad1)") (class "Default")
      (node (ref "R8") (pin "1") (pinfunction "1_1") (pintype "passive"))
      (node (ref "T2") (pin "B") (pinfunction "B_B") (pintype "passive"))
    )
    (net (code "69") (name "Net-(R9-Pad1)") (class "Default")
      (node (ref "R9") (pin "1") (pinfunction "1_1") (pintype "passive"))
      (node (ref "T1") (pin "B") (pinfunction "B_B") (pintype "passive"))
    )
    (net (code "70") (name "Net-(R11-Pad1)") (class "Default")
      (node (ref "R11") (pin "1") (pinfunction "1_1") (pintype "passive"))
      (node (ref "T4") (pin "B") (pinfunction "B_B") (pintype "passive"))
    )
    (net (code "71") (name "Net-(R12-Pad1)") (class "Default")
      (node (ref "R12") (pin "1") (pinfunction "1_1") (pintype "passive"))
      (node (ref "T3") (pin "B") (pinfunction "B_B") (pintype "passive"))
    )
    (net (code "72") (name "Net-(R14-Pad1)") (class "Default")
      (node (ref "R14") (pin "1") (pinfunction "1_1") (pintype "passive"))
      (node (ref "T6") (pin "B") (pinfunction "B_B") (pintype "passive"))
    )
    (net (code "73") (name "Net-(R15-Pad1)") (class "Default")
      (node (ref "R15") (pin "1") (pinfunction "1_1") (pintype "passive"))
      (node (ref "T5") (pin "B") (pinfunction "B_B") (pintype "passive"))
    )
    (net (code "74") (name "Net-(R17-Pad1)") (class "Default")
      (node (ref "R17") (pin "1") (pinfunction "1_1") (pintype "passive"))
      (node (ref "T8") (pin "B") (pinfunction "B_B") (pintype "passive"))
    )
    (net (code "75") (name "Net-(R18-Pad1)") (class "Default")
      (node (ref "R18") (pin "1") (pinfunction "1_1") (pintype "passive"))
      (node (ref "T7") (pin "B") (pinfunction "B_B") (pintype "passive"))
    )
    (net (code "76") (name "Net-(R20-Pad1)") (class "Default")
      (node (ref "R20") (pin "1") (pinfunction "1_1") (pintype "passive"))
      (node (ref "T10") (pin "B") (pinfunction "B_B") (pintype "passive"))
    )
    (net (code "77") (name "Net-(R21-Pad1)") (class "Default")
      (node (ref "R21") (pin "1") (pinfunction "1_1") (pintype "passive"))
      (node (ref "T9") (pin "B") (pinfunction "B_B") (pintype "passive"))
    )
    (net (code "78") (name "Net-(R23-Pad1)") (class "Default")
      (node (ref "R23") (pin "1") (pinfunction "1_1") (pintype "passive"))
      (node (ref "T12") (pin "B") (pinfunction "B_B") (pintype "passive"))
    )
    (net (code "79") (name "Net-(R24-Pad1)") (class "Default")
      (node (ref "R24") (pin "1") (pinfunction "1_1") (pintype "passive"))
      (node (ref "T11") (pin "B") (pinfunction "B_B") (pintype "passive"))
    )
    (net (code "80") (name "Net-(R26-Pad1)") (class "Default")
      (node (ref "R26") (pin "1") (pinfunction "1_1") (pintype "passive"))
      (node (ref "T14") (pin "B") (pinfunction "B_B") (pintype "passive"))
    )
    (net (code "81") (name "Net-(R27-Pad1)") (class "Default")
      (node (ref "R27") (pin "1") (pinfunction "1_1") (pintype "passive"))
      (node (ref "T13") (pin "B") (pinfunction "B_B") (pintype "passive"))
    )
    (net (code "82") (name "Net-(R29-Pad1)") (class "Default")
      (node (ref "R29") (pin "1") (pinfunction "1_1") (pintype "passive"))
      (node (ref "T16") (pin "B") (pinfunction "B_B") (pintype "passive"))
    )
    (net (code "83") (name "Net-(R30-Pad1)") (class "Default")
      (node (ref "R30") (pin "1") (pinfunction "1_1") (pintype "passive"))
      (node (ref "T15") (pin "B") (pinfunction "B_B") (pintype "passive"))
    )
    (net (code "84") (name "VCC") (class "Default")
      (node (ref "C1") (pin "1") (pinfunction "1_1") (pintype "passive"))
      (node (ref "C10") (pin "1") (pinfunction "1_1") (pintype "passive"))
      (node (ref "C11") (pin "1") (pinfunction "1_1") (pintype "passive"))
      (node (ref "C2") (pin "1") (pinfunction "1_1") (pintype "passive"))
      (node (ref "C3") (pin "2") (pinfunction "2_2") (pintype "passive"))
      (node (ref "C4") (pin "1") (pinfunction "1_1") (pintype "passive"))
      (node (ref "C5") (pin "1") (pinfunction "1_1") (pintype "passive"))
      (node (ref "C6") (pin "1") (pinfunction "1_1") (pintype "passive"))
      (node (ref "C7") (pin "1") (pinfunction "1_1") (pintype "passive"))
      (node (ref "C8") (pin "1") (pinfunction "1_1") (pintype "passive"))
      (node (ref "C9") (pin "1") (pinfunction "1_1") (pintype "passive"))
      (node (ref "IC1") (pin "1") (pinfunction "CLR_1") (pintype "input"))
      (node (ref "IC1") (pin "14") (pinfunction "VCC_14") (pintype "power_in"))
      (node (ref "IC1") (pin "4") (pinfunction "PRE_4") (pintype "input"))
      (node (ref "IC10") (pin "14") (pinfunction "VCC_14") (pintype "power_in"))
      (node (ref "IC2") (pin "16") (pinfunction "VCC_16") (pintype "power_in"))
      (node (ref "IC2") (pin "2") (pinfunction "B_2") (pintype "input"))
      (node (ref "IC3") (pin "8") (pinfunction "VCC_8") (pintype "power_in"))
      (node (ref "IC4") (pin "14") (pinfunction "VCC_14") (pintype "power_in"))
      (node (ref "IC5") (pin "14") (pinfunction "VCC_14") (pintype "power_in"))
      (node (ref "IC6") (pin "14") (pinfunction "VCC_14") (pintype "power_in"))
      (node (ref "IC7") (pin "14") (pinfunction "VCC_14") (pintype "power_in"))
      (node (ref "IC8") (pin "14") (pinfunction "VCC_14") (pintype "power_in"))
      (node (ref "IC9") (pin "14") (pinfunction "VCC_14") (pintype "power_in"))
      (node (ref "JP4") (pin "4") (pinfunction "4_4") (pintype "passive"))
      (node (ref "R1") (pin "2") (pinfunction "2_2") (pintype "passive"))
      (node (ref "R31") (pin "1") (pinfunction "1_1") (pintype "passive"))
      (node (ref "R32") (pin "2") (pinfunction "2_2") (pintype "passive"))
      (node (ref "R33") (pin "2") (pinfunction "2_2") (pintype "passive"))
      (node (ref "R34") (pin "1") (pinfunction "1_1") (pintype "passive"))
      (node (ref "R4") (pin "2") (pinfunction "2_2") (pintype "passive"))
      (node (ref "T10") (pin "E") (pinfunction "E_E") (pintype "passive"))
      (node (ref "T12") (pin "E") (pinfunction "E_E") (pintype "passive"))
      (node (ref "T14") (pin "E") (pinfunction "E_E") (pintype "passive"))
      (node (ref "T16") (pin "E") (pinfunction "E_E") (pintype "passive"))
      (node (ref "T2") (pin "E") (pinfunction "E_E") (pintype "passive"))
      (node (ref "T4") (pin "E") (pinfunction "E_E") (pintype "passive"))
      (node (ref "T6") (pin "E") (pinfunction "E_E") (pintype "passive"))
      (node (ref "T8") (pin "E") (pinfunction "E_E") (pintype "passive"))
    )
    (net (code "85") (name "unconnected-(IC1A-~{Q}-Pad6)") (class "Default")
      (node (ref "IC1") (pin "6") (pinfunction "~{Q}_6") (pintype "output"))
    )
    (net (code "86") (name "unconnected-(IC1B-Q-Pad9)") (class "Default")
      (node (ref "IC1") (pin "9") (pinfunction "Q_9") (pintype "output"))
    )
    (net (code "87") (name "unconnected-(IC1B-~{Q}-Pad8)") (class "Default")
      (node (ref "IC1") (pin "8") (pinfunction "~{Q}_8") (pintype "output"))
    )
    (net (code "88") (name "unconnected-(IC2A-Q-Pad13)") (class "Default")
      (node (ref "IC2") (pin "13") (pinfunction "Q_13") (pintype "output"))
    )
    (net (code "89") (name "unconnected-(IC2B-Q-Pad5)") (class "Default")
      (node (ref "IC2") (pin "5") (pinfunction "Q_5") (pintype "output"))
    )
    (net (code "90") (name "unconnected-(IC2B-~{Q}-Pad12)") (class "Default")
      (node (ref "IC2") (pin "12") (pinfunction "~{Q}_12") (pintype "output"))
    )
    (net (code "91") (name "unconnected-(IC6C-O-Pad8)") (class "Default")
      (node (ref "IC6") (pin "8") (pinfunction "O_8") (pintype "output"))
    )
    (net (code "92") (name "unconnected-(IC6D-O-Pad11)") (class "Default")
      (node (ref "IC6") (pin "11") (pinfunction "O_11") (pintype "output"))
    )
    (net (code "93") (name "unconnected-(JP1-Pad1)") (class "Default")
      (node (ref "JP1") (pin "1") (pinfunction "1_1") (pintype "passive"))
    )
    (net (code "94") (name "unconnected-(JP1-Pad2)") (class "Default")
      (node (ref "JP1") (pin "2") (pinfunction "2_2") (pintype "passive"))
    )
    (net (code "95") (name "unconnected-(JP2-Pad3)") (class "Default")
      (node (ref "JP2") (pin "3") (pinfunction "3_3") (pintype "passive"))
    )
    (net (code "96") (name "unconnected-(JP2-Pad4)") (class "Default")
      (node (ref "JP2") (pin "4") (pinfunction "4_4") (pintype "passive"))
    )
    (net (code "97") (name "unconnected-(JP2-Pad5)") (class "Default")
      (node (ref "JP2") (pin "5") (pinfunction "5_5") (pintype "passive"))
    )
    (net (code "98") (name "unconnected-(JP2-Pad6)") (class "Default")
      (node (ref "JP2") (pin "6") (pinfunction "6_6") (pintype "passive"))
    )
    (net (code "99") (name "unconnected-(JP2-Pad7)") (class "Default")
      (node (ref "JP2") (pin "7") (pinfunction "7_7") (pintype "passive"))
    )
    (net (code "100") (name "unconnected-(JP2-Pad8)") (class "Default")
      (node (ref "JP2") (pin "8") (pinfunction "8_8") (pintype "passive"))
    )
    (net (code "101") (name "unconnected-(JP4-Pad1)") (class "Default")
      (node (ref "JP4") (pin "1") (pinfunction "1_1") (pintype "passive"))
    )
    (net (code "102") (name "unconnected-(JP4-Pad2)") (class "Default")
      (node (ref "JP4") (pin "2") (pinfunction "2_2") (pintype "passive"))
    )
    (net (code "103") (name "unconnected-(JP4-Pad5)") (class "Default")
      (node (ref "JP4") (pin "5") (pinfunction "5_5") (pintype "passive"))
    )
    (net (code "104") (name "unconnected-(JP4-Pad6)") (class "Default")
      (node (ref "JP4") (pin "6") (pinfunction "6_6") (pintype "passive"))
    )
    (net (code "105") (name "unconnected-(JP5-Pad1)") (class "Default")
      (node (ref "JP5") (pin "1") (pinfunction "1_1") (pintype "passive"))
    )
    (net (code "106") (name "unconnected-(JP5-Pad2)") (class "Default")
      (node (ref "JP5") (pin "2") (pinfunction "2_2") (pintype "passive"))
    )
    (net (code "107") (name "unconnected-(JP5-Pad3)") (class "Default")
      (node (ref "JP5") (pin "3") (pinfunction "3_3") (pintype "passive"))
    )
    (net (code "108") (name "unconnected-(JP5-Pad4)") (class "Default")
      (node (ref "JP5") (pin "4") (pinfunction "4_4") (pintype "passive"))
    )
    (net (code "109") (name "unconnected-(JP5-Pad5)") (class "Default")
      (node (ref "JP5") (pin "5") (pinfunction "5_5") (pintype "passive"))
    )
    (net (code "110") (name "unconnected-(JP5-Pad6)") (class "Default")
      (node (ref "JP5") (pin "6") (pinfunction "6_6") (pintype "passive"))
    )
  )
)
